# laser_source_opamp.net
KiCad netlist of a schematic drawn in EAGLE
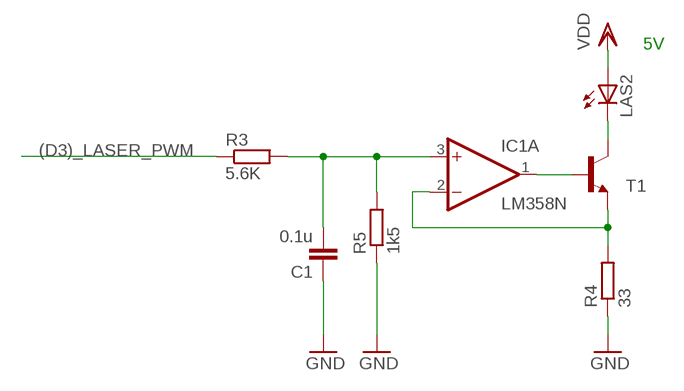
[diagram p0: schematic, sheet 1]

(export (version "E")
  (design (tool "Eeschema 10.0.6"))
  (components
    (comp (ref "C1")
      (value "0.1u")
      (footprint "eagle-import:C5B3.5")
      (libsource (lib "eagle-import") (part "C5/3.5"))
    )
    (comp (ref "IC1")
      (value "LM358N")
      (footprint "eagle-import:DIL08")
      (libsource (lib "eagle-import") (part "LM358N"))
    )
    (comp (ref "LAS2")
      (value "LED")
      (footprint "eagle-import:SMARTLED-TTW")
      (libsource (lib "eagle-import") (part "LED"))
    )
    (comp (ref "R3")
      (value "5.6K")
      (footprint "eagle-import:0204_5")
      (libsource (lib "eagle-import") (part "R-EU_0204/5"))
    )
    (comp (ref "R4")
      (value "33")
      (footprint "eagle-import:0204_5")
      (libsource (lib "eagle-import") (part "R-EU_0204/5"))
    )
    (comp (ref "R5")
      (value "1k5")
      (footprint "eagle-import:0204_5")
      (libsource (lib "eagle-import") (part "R-EU_0204/5"))
    )
    (comp (ref "T1")
      (value "-NPN-SOT89-BCE")
      (footprint "eagle-import:SOT89-BCE")
      (libsource (lib "eagle-import") (part "-NPN-SOT89-BCE"))
    )
  )
  (nets
    (net (code "1") (name "/(D3)_LASER_PWM") (class "Default")
      (node (ref "R3") (pin "1") (pinfunction "1_1") (pintype "passive"))
    )
    (net (code "2") (name "GND") (class "Default")
      (node (ref "C1") (pin "1") (pinfunction "1_1") (pintype "passive"))
      (node (ref "R4") (pin "1") (pinfunction "1_1") (pintype "passive"))
      (node (ref "R5") (pin "1") (pinfunction "1_1") (pintype "passive"))
    )
    (net (code "3") (name "Net-(IC1A-+IN)") (class "Default")
      (node (ref "C1") (pin "2") (pinfunction "2_2") (pintype "passive"))
      (node (ref "IC1") (pin "3") (pinfunction "+IN_3") (pintype "input"))
      (node (ref "R3") (pin "2") (pinfunction "2_2") (pintype "passive"))
      (node (ref "R5") (pin "2") (pinfunction "2_2") (pintype "passive"))
    )
    (net (code "4") (name "Net-(IC1A--IN)") (class "Default")
      (node (ref "IC1") (pin "2") (pinfunction "-IN_2") (pintype "input"))
      (node (ref "R4") (pin "2") (pinfunction "2_2") (pintype "passive"))
      (node (ref "T1") (pin "E") (pinfunction "E_E") (pintype "passive"))
    )
    (net (code "5") (name "Net-(IC1A-OUT)") (class "Default")
      (node (ref "IC1") (pin "1") (pinfunction "OUT_1") (pintype "output"))
      (node (ref "T1") (pin "B") (pinfunction "B_B") (pintype "passive"))
    )
    (net (code "6") (name "Net-(LAS2-C)") (class "Default")
      (node (ref "LAS2") (pin "C@1") (pinfunction "C_C@1") (pintype "passive"))
      (node (ref "T1") (pin "C") (pinfunction "C_C") (pintype "passive"))
    )
    (net (code "7") (name "VDD") (class "Default")
      (node (ref "LAS2") (pin "A@1") (pinfunction "A_A@1") (pintype "passive"))
    )
  )
)
